# RS485_Adapter.net
KiCad netlist of a schematic drawn in EAGLE
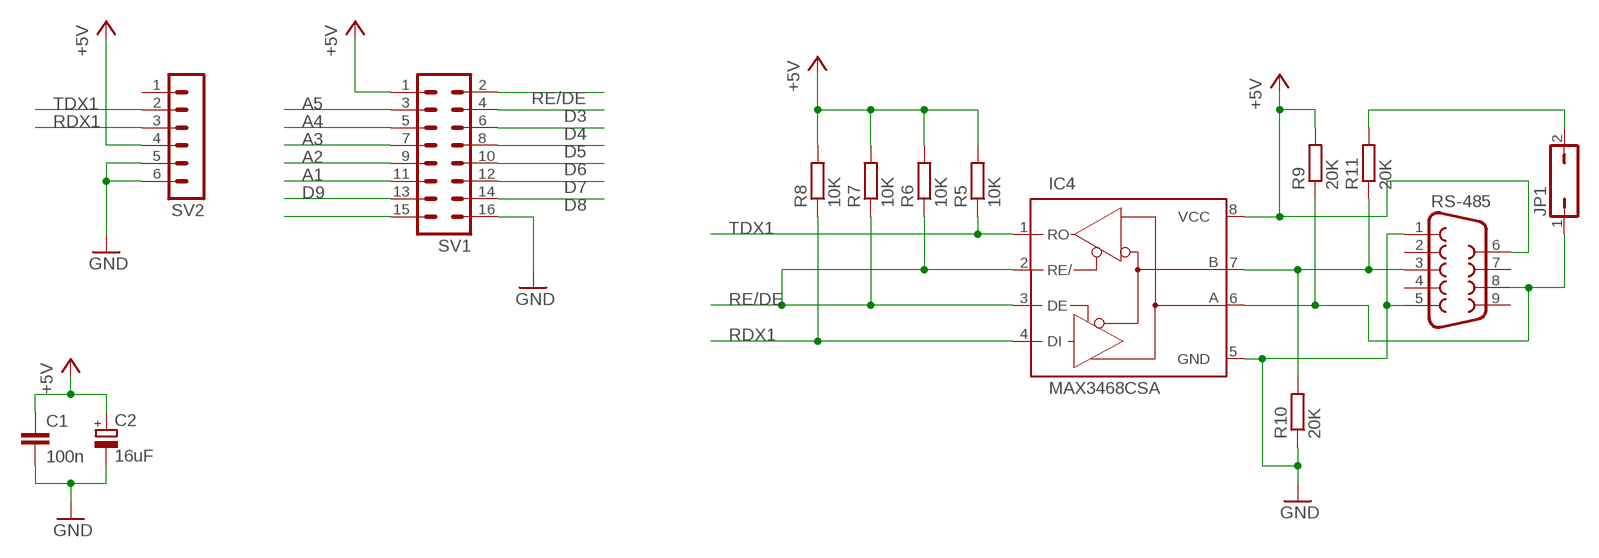
[diagram p0: schematic, sheet 1]

(export (version "E")
  (design (tool "Eeschema 10.0.6"))
  (components
    (comp (ref "C1")
      (value "100n")
      (footprint "eagle-import:C0402")
      (libsource (lib "eagle-import") (part "C-EUC0402"))
    )
    (comp (ref "C2")
      (value "16uF")
      (footprint "eagle-import:A_3216-18R")
      (libsource (lib "eagle-import") (part "CPOL-EUA/3216-18R"))
    )
    (comp (ref "IC4")
      (value "MAX3468CSA")
      (footprint "eagle-import:SO08")
      (fields (field (name "MPN") "MAX3468CSA+"))
      (libsource (lib "eagle-import") (part "MAX34SA68C"))
    )
    (comp (ref "JP1")
      (value "JP1Q")
      (footprint "eagle-import:JP1")
      (libsource (lib "eagle-import") (part "JP1Q"))
    )
    (comp (ref "R5")
      (value "10K")
      (footprint "eagle-import:MINI_MELF-0102R")
      (libsource (lib "eagle-import") (part "R-EU_MELF0102R"))
    )
    (comp (ref "R6")
      (value "10K")
      (footprint "eagle-import:MINI_MELF-0102R")
      (libsource (lib "eagle-import") (part "R-EU_MELF0102R"))
    )
    (comp (ref "R7")
      (value "10K")
      (footprint "eagle-import:MINI_MELF-0102R")
      (libsource (lib "eagle-import") (part "R-EU_MELF0102R"))
    )
    (comp (ref "R8")
      (value "10K")
      (footprint "eagle-import:MINI_MELF-0102R")
      (libsource (lib "eagle-import") (part "R-EU_MELF0102R"))
    )
    (comp (ref "R9")
      (value "20K")
      (footprint "eagle-import:MINI_MELF-0102R")
      (libsource (lib "eagle-import") (part "R-EU_MELF0102R"))
    )
    (comp (ref "R10")
      (value "20K")
      (footprint "eagle-import:MINI_MELF-0102R")
      (libsource (lib "eagle-import") (part "R-EU_MELF0102R"))
    )
    (comp (ref "R11")
      (value "20K")
      (footprint "eagle-import:MINI_MELF-0102R")
      (libsource (lib "eagle-import") (part "R-EU_MELF0102R"))
    )
    (comp (ref "RS-485")
      (value "F09V")
      (footprint "eagle-import:F09V")
      (libsource (lib "eagle-import") (part "F09V"))
    )
    (comp (ref "SV1")
      (value "MA08-2")
      (footprint "eagle-import:MA08-2")
      (libsource (lib "eagle-import") (part "MA08-2"))
    )
    (comp (ref "SV2")
      (value "MA06-1")
      (footprint "eagle-import:MA06-1")
      (libsource (lib "eagle-import") (part "MA06-1"))
    )
  )
  (nets
    (net (code "1") (name "+5V") (class "Default")
      (node (ref "C1") (pin "1") (pinfunction "1_1") (pintype "passive"))
      (node (ref "C2") (pin "+") (pinfunction "+_+") (pintype "passive"))
      (node (ref "IC4") (pin "8") (pinfunction "VCC_8") (pintype "power_in"))
      (node (ref "R5") (pin "2") (pinfunction "2_2") (pintype "passive"))
      (node (ref "R6") (pin "2") (pinfunction "2_2") (pintype "passive"))
      (node (ref "R7") (pin "2") (pinfunction "2_2") (pintype "passive"))
      (node (ref "R8") (pin "2") (pinfunction "2_2") (pintype "passive"))
      (node (ref "R9") (pin "2") (pinfunction "2_2") (pintype "passive"))
      (node (ref "RS-485") (pin "6") (pinfunction "6_6") (pintype "passive"))
      (node (ref "SV1") (pin "1") (pinfunction "1_1") (pintype "passive"))
      (node (ref "SV2") (pin "4") (pinfunction "4_4") (pintype "passive"))
    )
    (net (code "2") (name "/A1") (class "Default")
      (node (ref "SV1") (pin "11") (pinfunction "11_11") (pintype "passive"))
    )
    (net (code "3") (name "/A2") (class "Default")
      (node (ref "SV1") (pin "9") (pinfunction "9_9") (pintype "passive"))
    )
    (net (code "4") (name "/A3") (class "Default")
      (node (ref "SV1") (pin "7") (pinfunction "7_7") (pintype "passive"))
    )
    (net (code "5") (name "/A4") (class "Default")
      (node (ref "SV1") (pin "5") (pinfunction "5_5") (pintype "passive"))
    )
    (net (code "6") (name "/A5") (class "Default")
      (node (ref "SV1") (pin "3") (pinfunction "3_3") (pintype "passive"))
    )
    (net (code "7") (name "/D3") (class "Default")
      (node (ref "SV1") (pin "4") (pinfunction "4_4") (pintype "passive"))
    )
    (net (code "8") (name "/D4") (class "Default")
      (node (ref "SV1") (pin "6") (pinfunction "6_6") (pintype "passive"))
    )
    (net (code "9") (name "/D5") (class "Default")
      (node (ref "SV1") (pin "8") (pinfunction "8_8") (pintype "passive"))
    )
    (net (code "10") (name "/D6") (class "Default")
      (node (ref "SV1") (pin "10") (pinfunction "10_10") (pintype "passive"))
    )
    (net (code "11") (name "/D7") (class "Default")
      (node (ref "SV1") (pin "12") (pinfunction "12_12") (pintype "passive"))
    )
    (net (code "12") (name "/D8") (class "Default")
      (node (ref "SV1") (pin "14") (pinfunction "14_14") (pintype "passive"))
    )
    (net (code "13") (name "/D9") (class "Default")
      (node (ref "SV1") (pin "13") (pinfunction "13_13") (pintype "passive"))
    )
    (net (code "14") (name "/RDX1") (class "Default")
      (node (ref "IC4") (pin "4") (pinfunction "DI_4") (pintype "input"))
      (node (ref "R8") (pin "1") (pinfunction "1_1") (pintype "passive"))
      (node (ref "SV2") (pin "3") (pinfunction "3_3") (pintype "passive"))
    )
    (net (code "15") (name "/RE{slash}DE") (class "Default")
      (node (ref "IC4") (pin "2") (pinfunction "RE/_2") (pintype "input"))
      (node (ref "IC4") (pin "3") (pinfunction "DE_3") (pintype "input"))
      (node (ref "R6") (pin "1") (pinfunction "1_1") (pintype "passive"))
      (node (ref "R7") (pin "1") (pinfunction "1_1") (pintype "passive"))
      (node (ref "SV1") (pin "2") (pinfunction "2_2") (pintype "passive"))
    )
    (net (code "16") (name "/TDX1") (class "Default")
      (node (ref "IC4") (pin "1") (pinfunction "RO_1") (pintype "output"))
      (node (ref "R5") (pin "1") (pinfunction "1_1") (pintype "passive"))
      (node (ref "SV2") (pin "2") (pinfunction "2_2") (pintype "passive"))
    )
    (net (code "17") (name "GND") (class "Default")
      (node (ref "C1") (pin "2") (pinfunction "2_2") (pintype "passive"))
      (node (ref "C2") (pin "-") (pinfunction "-_-") (pintype "passive"))
      (node (ref "IC4") (pin "5") (pinfunction "GND_5") (pintype "power_in"))
      (node (ref "R10") (pin "1") (pinfunction "1_1") (pintype "passive"))
      (node (ref "RS-485") (pin "1") (pinfunction "1_1") (pintype "passive"))
      (node (ref "RS-485") (pin "5") (pinfunction "5_5") (pintype "passive"))
      (node (ref "SV1") (pin "16") (pinfunction "16_16") (pintype "passive"))
      (node (ref "SV2") (pin "5") (pinfunction "5_5") (pintype "passive"))
      (node (ref "SV2") (pin "6") (pinfunction "6_6") (pintype "passive"))
    )
    (net (code "18") (name "Net-(IC4-A)") (class "Default")
      (node (ref "IC4") (pin "6") (pinfunction "A_6") (pintype "passive"))
      (node (ref "JP1") (pin "1") (pinfunction "1_1") (pintype "passive"))
      (node (ref "R9") (pin "1") (pinfunction "1_1") (pintype "passive"))
      (node (ref "RS-485") (pin "8") (pinfunction "8_8") (pintype "passive"))
    )
    (net (code "19") (name "Net-(IC4-B)") (class "Default")
      (node (ref "IC4") (pin "7") (pinfunction "B_7") (pintype "passive"))
      (node (ref "R10") (pin "2") (pinfunction "2_2") (pintype "passive"))
      (node (ref "R11") (pin "1") (pinfunction "1_1") (pintype "passive"))
      (node (ref "RS-485") (pin "3") (pinfunction "3_3") (pintype "passive"))
    )
    (net (code "20") (name "Net-(JP1-Pad2)") (class "Default")
      (node (ref "JP1") (pin "2") (pinfunction "2_2") (pintype "passive"))
      (node (ref "R11") (pin "2") (pinfunction "2_2") (pintype "passive"))
    )
    (net (code "21") (name "unconnected-(RS-485-Pad2)") (class "Default")
      (node (ref "RS-485") (pin "2") (pinfunction "2_2") (pintype "passive"))
    )
    (net (code "22") (name "unconnected-(RS-485-Pad4)") (class "Default")
      (node (ref "RS-485") (pin "4") (pinfunction "4_4") (pintype "passive"))
    )
    (net (code "23") (name "unconnected-(RS-485-Pad7)") (class "Default")
      (node (ref "RS-485") (pin "7") (pinfunction "7_7") (pintype "passive"))
    )
    (net (code "24") (name "unconnected-(RS-485-Pad9)") (class "Default")
      (node (ref "RS-485") (pin "9") (pinfunction "9_9") (pintype "passive"))
    )
    (net (code "25") (name "unconnected-(SV1-Pad15)") (class "Default")
      (node (ref "SV1") (pin "15") (pinfunction "15_15") (pintype "passive"))
    )
    (net (code "26") (name "unconnected-(SV2-Pad1)") (class "Default")
      (node (ref "SV2") (pin "1") (pinfunction "1_1") (pintype "passive"))
    )
  )
)
